# Powering.net
KiCad netlist of a schematic drawn in Altium Designer
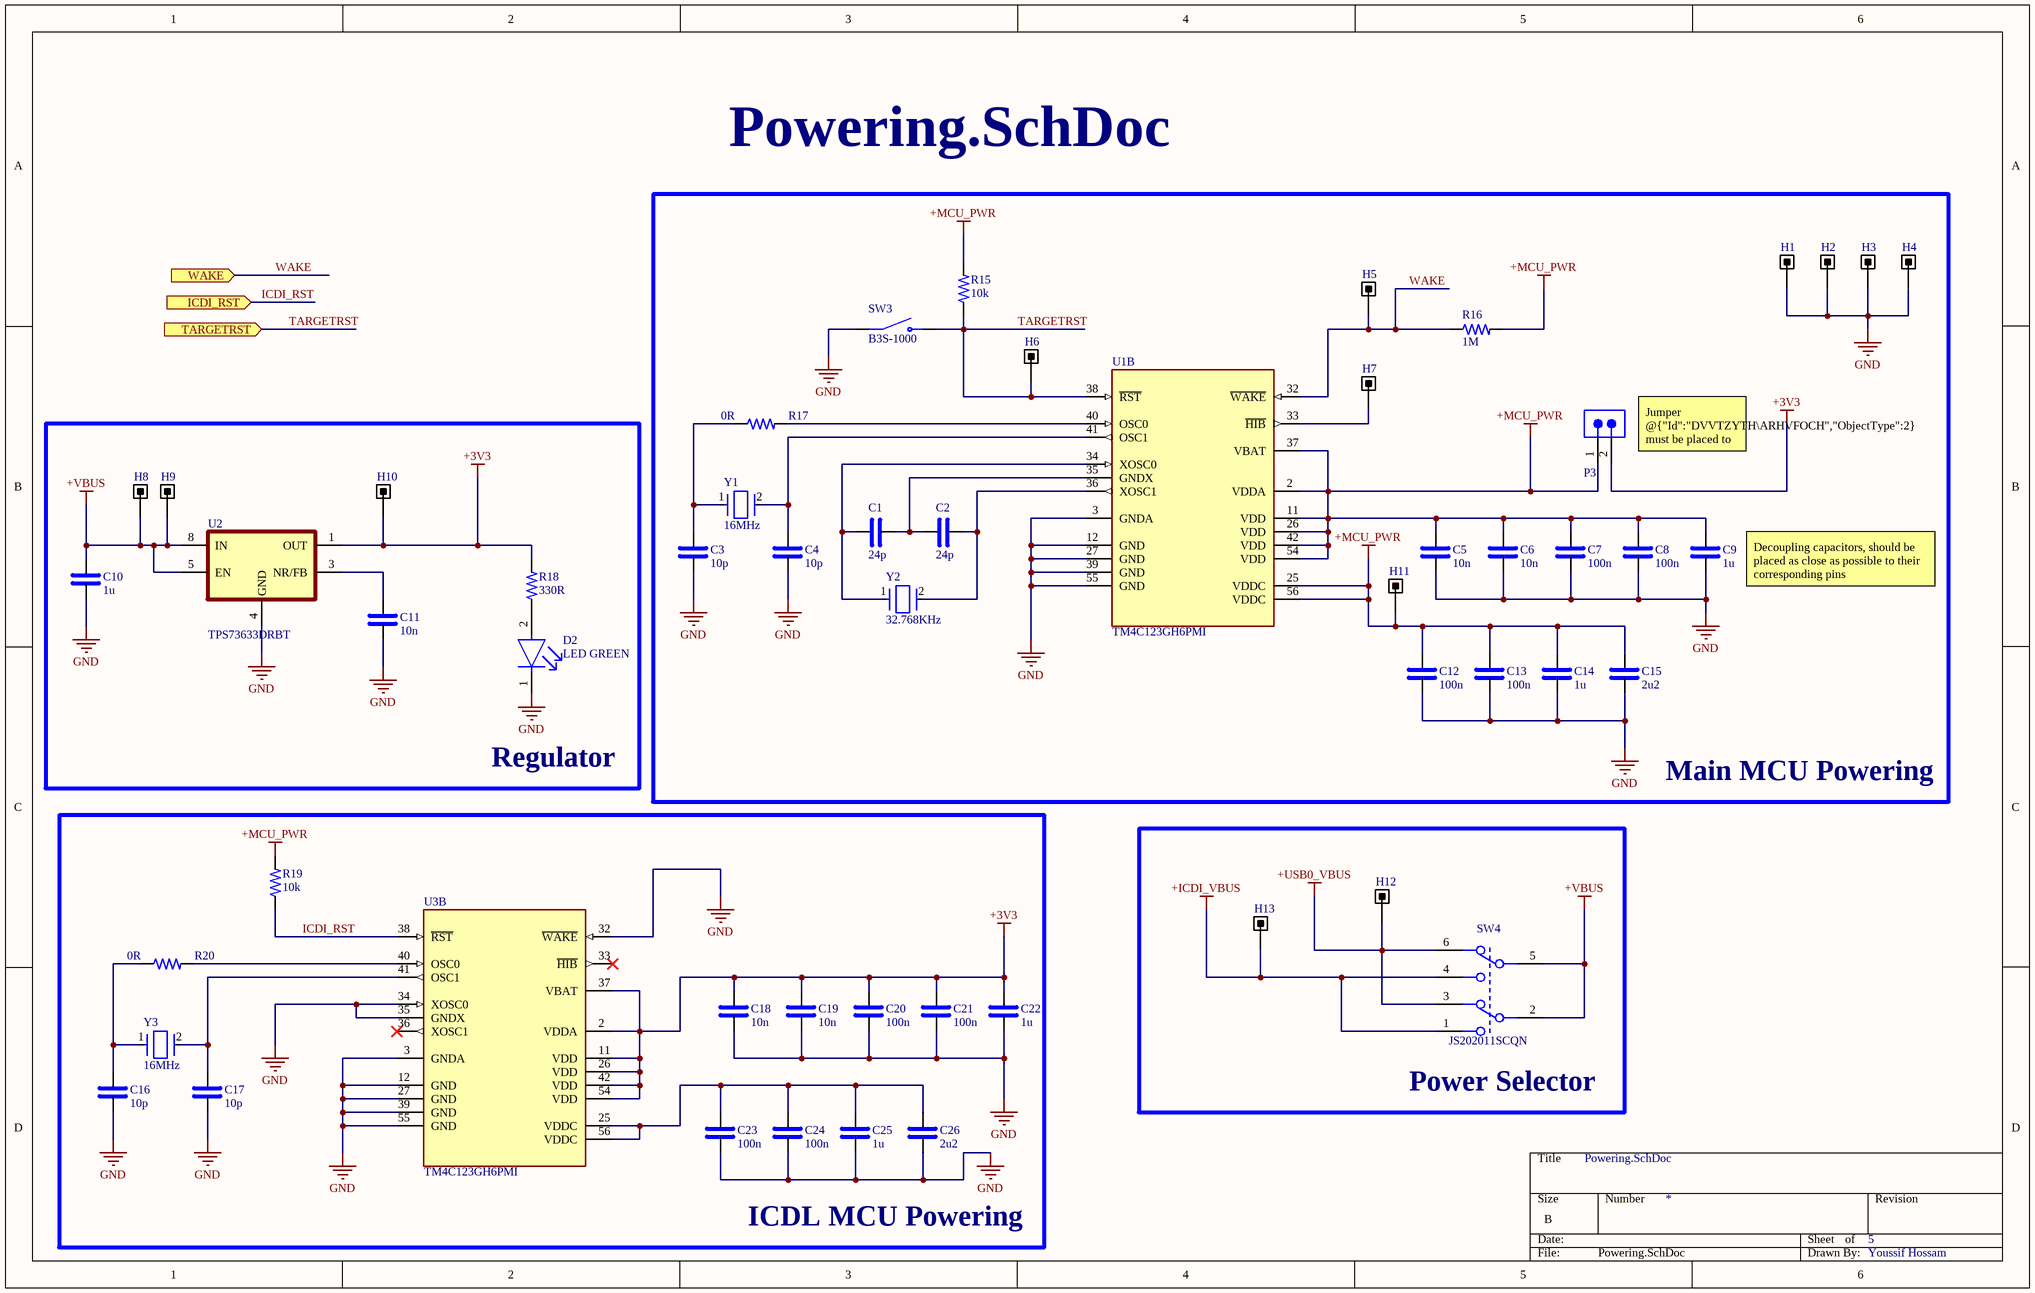
[diagram p0: Powering.SchDoc]

(export (version "E")
  (design (tool "Eeschema 10.0.6"))
  (components
    (comp (ref "C1")
      (value "24p")
      (footprint "0402 CAP")
      (description "24 pF ±5% 50V Ceramic Capacitor C0G, NP0 0402 (1005 Metric)")
      (fields (field (name "PART NUMBER") "C1005C0G1H240J") (field (name "VOLTAGE") "50V"))
      (libsource (lib "Integrated_Library") (part "0402 SMD Capacitor"))
    )
    (comp (ref "C2")
      (value "24p")
      (footprint "0402 CAP")
      (description "24 pF ±5% 50V Ceramic Capacitor C0G, NP0 0402 (1005 Metric)")
      (fields (field (name "PART NUMBER") "C1005C0G1H240J") (field (name "VOLTAGE") "50V"))
      (libsource (lib "Integrated_Library") (part "0402 SMD Capacitor"))
    )
    (comp (ref "C3")
      (value "10p")
      (footprint "0402 CAP")
      (description "10 pF ±5% 50V Ceramic Capacitor C0G, NP0 0402 (1005 Metric)")
      (fields (field (name "PART NUMBER") "GRM1555C1H100JZ01D") (field (name "VOLTAGE") "50V"))
      (libsource (lib "Integrated_Library") (part "0402 SMD Capacitor"))
    )
    (comp (ref "C4")
      (value "10p")
      (footprint "0402 CAP")
      (description "10 pF ±5% 50V Ceramic Capacitor C0G, NP0 0402 (1005 Metric)")
      (fields (field (name "PART NUMBER") "GRM1555C1H100JZ01D") (field (name "VOLTAGE") "50V"))
      (libsource (lib "Integrated_Library") (part "0402 SMD Capacitor"))
    )
    (comp (ref "C5")
      (value "10n")
      (footprint "0402 CAP")
      (fields
        (field (name "MANUFACTURER") "Taiyo Yuden")
        (field (name "MANUFACTURER PART NUMBER") "TMK105B7103KV-F")
      )
      (libsource (lib "Integrated_Library") (part "0402 SMD Capacitor"))
    )
    (comp (ref "C6")
      (value "10n")
      (footprint "0402 CAP")
      (fields
        (field (name "MANUFACTURER") "Taiyo Yuden")
        (field (name "MANUFACTURER PART NUMBER") "TMK105B7103KV-F")
      )
      (libsource (lib "Integrated_Library") (part "0402 SMD Capacitor"))
    )
    (comp (ref "C7")
      (value "100n")
      (footprint "0402 CAP")
      (fields
        (field (name "MANUFACTURER") "Taiyo Yuden")
        (field (name "MANUFACTURER PART NUMBER") "EMK105B7104KV-F")
      )
      (libsource (lib "Integrated_Library") (part "0402 SMD Capacitor"))
    )
    (comp (ref "C8")
      (value "100n")
      (footprint "0402 CAP")
      (fields
        (field (name "MANUFACTURER") "Taiyo Yuden")
        (field (name "MANUFACTURER PART NUMBER") "EMK105B7104KV-F")
      )
      (libsource (lib "Integrated_Library") (part "0402 SMD Capacitor"))
    )
    (comp (ref "C9")
      (value "1u")
      (footprint "0402 CAP")
      (description "Ceramic Capacitor, Ceramic, 10V, 10% +Tol, 10% -Tol, X5R, 15% TC, 1uF, Surface Mount, 0402")
      (fields
        (field (name "MANUFACTURER") "Johanson")
        (field (name "MANUFACTURER PART NUMBER") "100R07X105KV4T")
      )
      (libsource (lib "Integrated_Library") (part "0402 SMD Capacitor"))
    )
    (comp (ref "C10")
      (value "1u")
      (footprint "0402 CAP")
      (description "Ceramic Capacitor, Ceramic, 10V, 10% +Tol, 10% -Tol, X5R, 15% TC, 1uF, Surface Mount, 0402")
      (fields
        (field (name "MANUFACTURER") "Johanson")
        (field (name "MANUFACTURER PART NUMBER") "100R07X105KV4T")
      )
      (libsource (lib "Integrated_Library") (part "0402 SMD Capacitor"))
    )
    (comp (ref "C11")
      (value "10n")
      (footprint "0402 CAP")
      (fields
        (field (name "MANUFACTURER") "Taiyo Yuden")
        (field (name "MANUFACTURER PART NUMBER") "TMK105B7103KV-F")
      )
      (libsource (lib "Integrated_Library") (part "0402 SMD Capacitor"))
    )
    (comp (ref "C12")
      (value "100n")
      (footprint "0402 CAP")
      (fields
        (field (name "MANUFACTURER") "Taiyo Yuden")
        (field (name "MANUFACTURER PART NUMBER") "EMK105B7104KV-F")
      )
      (libsource (lib "Integrated_Library") (part "0402 SMD Capacitor"))
    )
    (comp (ref "C13")
      (value "100n")
      (footprint "0402 CAP")
      (fields
        (field (name "MANUFACTURER") "Taiyo Yuden")
        (field (name "MANUFACTURER PART NUMBER") "EMK105B7104KV-F")
      )
      (libsource (lib "Integrated_Library") (part "0402 SMD Capacitor"))
    )
    (comp (ref "C14")
      (value "1u")
      (footprint "0402 CAP")
      (description "Ceramic Capacitor, Ceramic, 10V, 10% +Tol, 10% -Tol, X5R, 15% TC, 1uF, Surface Mount, 0402")
      (fields
        (field (name "MANUFACTURER") "Johanson")
        (field (name "MANUFACTURER PART NUMBER") "100R07X105KV4T")
      )
      (libsource (lib "Integrated_Library") (part "0402 SMD Capacitor"))
    )
    (comp (ref "C15")
      (value "2u2")
      (footprint "FP-GCJ188-0_2-IPC_C")
      (fields
        (field (name "MANUFACTURER") "Murata")
        (field (name "MANUFACTURER PART NUMBER") "GRM188R61C225KE15D")
      )
      (libsource (lib "Integrated_Library") (part "0603 SMD CAP"))
    )
    (comp (ref "C16")
      (value "10p")
      (footprint "0402 CAP")
      (description "10 pF ±5% 50V Ceramic Capacitor C0G, NP0 0402 (1005 Metric)")
      (fields (field (name "PART NUMBER") "GRM1555C1H100JZ01D") (field (name "VOLTAGE") "50V"))
      (libsource (lib "Integrated_Library") (part "0402 SMD Capacitor"))
    )
    (comp (ref "C17")
      (value "10p")
      (footprint "0402 CAP")
      (description "10 pF ±5% 50V Ceramic Capacitor C0G, NP0 0402 (1005 Metric)")
      (fields (field (name "PART NUMBER") "GRM1555C1H100JZ01D") (field (name "VOLTAGE") "50V"))
      (libsource (lib "Integrated_Library") (part "0402 SMD Capacitor"))
    )
    (comp (ref "C18")
      (value "10n")
      (footprint "0402 CAP")
      (fields
        (field (name "MANUFACTURER") "Taiyo Yuden")
        (field (name "MANUFACTURER PART NUMBER") "TMK105B7103KV-F")
      )
      (libsource (lib "Integrated_Library") (part "0402 SMD Capacitor"))
    )
    (comp (ref "C19")
      (value "10n")
      (footprint "0402 CAP")
      (fields
        (field (name "MANUFACTURER") "Taiyo Yuden")
        (field (name "MANUFACTURER PART NUMBER") "TMK105B7103KV-F")
      )
      (libsource (lib "Integrated_Library") (part "0402 SMD Capacitor"))
    )
    (comp (ref "C20")
      (value "100n")
      (footprint "0402 CAP")
      (fields
        (field (name "MANUFACTURER") "Taiyo Yuden")
        (field (name "MANUFACTURER PART NUMBER") "EMK105B7104KV-F")
      )
      (libsource (lib "Integrated_Library") (part "0402 SMD Capacitor"))
    )
    (comp (ref "C21")
      (value "100n")
      (footprint "0402 CAP")
      (fields
        (field (name "MANUFACTURER") "Taiyo Yuden")
        (field (name "MANUFACTURER PART NUMBER") "EMK105B7104KV-F")
      )
      (libsource (lib "Integrated_Library") (part "0402 SMD Capacitor"))
    )
    (comp (ref "C22")
      (value "1u")
      (footprint "0402 CAP")
      (description "Ceramic Capacitor, Ceramic, 10V, 10% +Tol, 10% -Tol, X5R, 15% TC, 1uF, Surface Mount, 0402")
      (fields
        (field (name "MANUFACTURER") "Johanson")
        (field (name "MANUFACTURER PART NUMBER") "100R07X105KV4T")
      )
      (libsource (lib "Integrated_Library") (part "0402 SMD Capacitor"))
    )
    (comp (ref "C23")
      (value "100n")
      (footprint "0402 CAP")
      (fields
        (field (name "MANUFACTURER") "Taiyo Yuden")
        (field (name "MANUFACTURER PART NUMBER") "EMK105B7104KV-F")
      )
      (libsource (lib "Integrated_Library") (part "0402 SMD Capacitor"))
    )
    (comp (ref "C24")
      (value "100n")
      (footprint "0402 CAP")
      (fields
        (field (name "MANUFACTURER") "Taiyo Yuden")
        (field (name "MANUFACTURER PART NUMBER") "EMK105B7104KV-F")
      )
      (libsource (lib "Integrated_Library") (part "0402 SMD Capacitor"))
    )
    (comp (ref "C25")
      (value "1u")
      (footprint "0402 CAP")
      (description "Ceramic Capacitor, Ceramic, 10V, 10% +Tol, 10% -Tol, X5R, 15% TC, 1uF, Surface Mount, 0402")
      (fields
        (field (name "MANUFACTURER") "Johanson")
        (field (name "MANUFACTURER PART NUMBER") "100R07X105KV4T")
      )
      (libsource (lib "Integrated_Library") (part "0402 SMD Capacitor"))
    )
    (comp (ref "C26")
      (value "2u2")
      (footprint "FP-GCJ188-0_2-IPC_C")
      (fields
        (field (name "MANUFACTURER") "Murata")
        (field (name "MANUFACTURER PART NUMBER") "GRM188R61C225KE15D")
      )
      (libsource (lib "Integrated_Library") (part "0603 SMD CAP"))
    )
    (comp (ref "D2")
      (value "LED GREEN")
      (footprint "FP-LTST-C171GKT-MFG")
      (description "LED GREEN CLEAR CHIP SMD")
      (libsource (lib "Integrated_Library") (part "CMP-22017-000007-1"))
    )
    (comp (ref "H1")
      (value "Test Point")
      (footprint "Test Point")
      (libsource (lib "Integrated_Library") (part "Test Point"))
    )
    (comp (ref "H2")
      (value "Test Point")
      (footprint "Test Point")
      (libsource (lib "Integrated_Library") (part "Test Point"))
    )
    (comp (ref "H3")
      (value "Test Point")
      (footprint "Test Point")
      (libsource (lib "Integrated_Library") (part "Test Point"))
    )
    (comp (ref "H4")
      (value "Test Point")
      (footprint "Test Point")
      (libsource (lib "Integrated_Library") (part "Test Point"))
    )
    (comp (ref "H5")
      (value "Test Point")
      (footprint "Test Point")
      (libsource (lib "Integrated_Library") (part "Test Point"))
    )
    (comp (ref "H6")
      (value "Test Point")
      (footprint "Test Point")
      (libsource (lib "Integrated_Library") (part "Test Point"))
    )
    (comp (ref "H7")
      (value "Test Point")
      (footprint "Test Point")
      (libsource (lib "Integrated_Library") (part "Test Point"))
    )
    (comp (ref "H8")
      (value "Test Point")
      (footprint "Test Point")
      (libsource (lib "Integrated_Library") (part "Test Point"))
    )
    (comp (ref "H9")
      (value "Test Point")
      (footprint "Test Point")
      (libsource (lib "Integrated_Library") (part "Test Point"))
    )
    (comp (ref "H10")
      (value "Test Point")
      (footprint "Test Point")
      (libsource (lib "Integrated_Library") (part "Test Point"))
    )
    (comp (ref "H11")
      (value "Test Point")
      (footprint "Test Point")
      (libsource (lib "Integrated_Library") (part "Test Point"))
    )
    (comp (ref "H12")
      (value "Test Point")
      (footprint "Test Point")
      (libsource (lib "Integrated_Library") (part "Test Point"))
    )
    (comp (ref "H13")
      (value "Test Point")
      (footprint "Test Point")
      (libsource (lib "Integrated_Library") (part "Test Point"))
    )
    (comp (ref "P3")
      (value "61300211121")
      (footprint "61300211121")
      (description "WR-PHD Pin Header, THT, Vertical, pitch 2.54mm, 1 Row, 2P")
      (fields (field (name "MANUFACTURER") "Wurth Elektronik"))
      (libsource (lib "Altium_WR-PHD_rev24a") (part "61300211121"))
    )
    (comp (ref "R15")
      (value "10k")
      (footprint "0402 RES")
      (fields
        (field (name "MANUFACTURER") "Yageo")
        (field (name "MANUFACTURER PART NUMBER") "RC0402FR-0710KL")
        (field (name "POWER") "62.5mW")
      )
      (libsource (lib "Integrated_Library") (part "0402 SMD Resistor"))
    )
    (comp (ref "R16")
      (value "1M")
      (footprint "0402 RES")
      (description "1 MOhms ±1% 0.063W, 1/16W Chip Resistor 0402 (1005 Metric) Thick Film")
      (fields (field (name "PART NUMBER") "MCR01MRTF1004") (field (name "TOLERANCE") "±1%"))
      (libsource (lib "Integrated_Library") (part "0402 SMD Resistor"))
    )
    (comp (ref "R17")
      (value "0R")
      (footprint "FP-ERA3A-IPC_B")
      (description "Fixed Resistor, Metal Glaze/thick Film, 0.1W, 0ohm, Surface Mount, 0603")
      (fields
        (field (name "MANUFACTURER") "Panasonic")
        (field (name "MANUFACTURER PART NUMBER") "ERJ-3GEY0R00V")
      )
      (libsource (lib "Integrated_Library") (part "0603 SMD RES"))
    )
    (comp (ref "R18")
      (value "330R")
      (footprint "0402 RES")
      (fields
        (field (name "MANUFACTURER") "Vishay Dale")
        (field (name "MANUFACTURER PART NUMBER") "RCC0402330RFKED")
      )
      (libsource (lib "Integrated_Library") (part "0402 SMD Resistor"))
    )
    (comp (ref "R19")
      (value "10k")
      (footprint "0402 RES")
      (fields
        (field (name "MANUFACTURER") "Yageo")
        (field (name "MANUFACTURER PART NUMBER") "RC0402FR-0710KL")
        (field (name "POWER") "62.5mW")
      )
      (libsource (lib "Integrated_Library") (part "0402 SMD Resistor"))
    )
    (comp (ref "R20")
      (value "0R")
      (footprint "FP-ERA3A-IPC_B")
      (description "Fixed Resistor, Metal Glaze/thick Film, 0.1W, 0ohm, Surface Mount, 0603")
      (fields
        (field (name "MANUFACTURER") "Panasonic")
        (field (name "MANUFACTURER PART NUMBER") "ERJ-3GEY0R00V")
      )
      (libsource (lib "Integrated_Library") (part "0603 SMD RES"))
    )
    (comp (ref "SW3")
      (value "B3S-1000")
      (footprint "SW_B3S-1000")
      (description "Tactile Switch SPST-NO Top Actuated Surface Mount")
      (fields (field (name "MF") "Omron"))
      (libsource (lib "Integrated_Library") (part "B3S-1000"))
    )
    (comp (ref "SW4")
      (value "JS202011SCQN")
      (footprint "FP-JS202011SCQN-MFG")
      (description "SWITCH SLIDE DPDT 300MA 6V")
      (libsource (lib "Integrated_Library") (part "CMP-2000-05087-3"))
    )
    (comp (ref "U1")
      (value "TM4C123GH6PMI")
      (footprint "QFP50P1200X1200X160-64N")
      (fields (field (name "MF") "Texas Instruments"))
      (libsource (lib "Integrated_Library") (part "TM4C123GH6PMI"))
    )
    (comp (ref "U2")
      (value "TPS73633DRBT")
      (footprint "IC_DRV8601DRBT")
      (libsource (lib "Integrated_Library") (part "TPS73633DRBT"))
    )
    (comp (ref "U3")
      (value "TM4C123GH6PMI")
      (footprint "QFP50P1200X1200X160-64N")
      (fields (field (name "MF") "Texas Instruments"))
      (libsource (lib "Integrated_Library") (part "TM4C123GH6PMI"))
    )
    (comp (ref "Y1")
      (value "16MHz")
      (footprint "FP-ABM3-MFG")
      (description "Crystal 16MHz ±20ppm 18pF SMD-2 5mm x 3.2mm")
      (fields (field (name "TOLERANCE") "20ppm"))
      (libsource (lib "Integrated_Library") (part "CMP-27762-013555-1"))
    )
    (comp (ref "Y2")
      (value "32.768KHz")
      (footprint "FP-AB26TRB-MFG")
      (description "CRYSTAL 32.7680KHZ 12.5PF TH")
      (fields (field (name "TOLERANCE") "20ppm"))
      (libsource (lib "Integrated_Library") (part "CMP-27762-006068-1"))
    )
    (comp (ref "Y3")
      (value "16MHz")
      (footprint "FP-ABM3-MFG")
      (description "Crystal 16MHz ±20ppm 18pF SMD-2 5mm x 3.2mm")
      (fields (field (name "TOLERANCE") "20ppm"))
      (libsource (lib "Integrated_Library") (part "CMP-27762-013555-1"))
    )
  )
  (nets
    (net (code "1") (name "+3V3") (class "Default")
      (node (ref "C18") (pin "2") (pinfunction "2_2") (pintype "passive"))
      (node (ref "C19") (pin "2") (pinfunction "2_2") (pintype "passive"))
      (node (ref "C20") (pin "2") (pinfunction "2_2") (pintype "passive"))
      (node (ref "C21") (pin "2") (pinfunction "2_2") (pintype "passive"))
      (node (ref "C22") (pin "2") (pinfunction "2_2") (pintype "passive"))
      (node (ref "H10") (pin "1") (pinfunction "1_1") (pintype "passive"))
      (node (ref "P3") (pin "2") (pinfunction "2_2") (pintype "passive"))
      (node (ref "R18") (pin "2") (pinfunction "2_2") (pintype "passive"))
      (node (ref "U2") (pin "1") (pinfunction "OUT_1") (pintype "power_in"))
      (node (ref "U3") (pin "11") (pinfunction "VDD_11") (pintype "power_in"))
      (node (ref "U3") (pin "2") (pinfunction "VDDA_2") (pintype "power_in"))
      (node (ref "U3") (pin "26") (pinfunction "VDD_26") (pintype "power_in"))
      (node (ref "U3") (pin "37") (pinfunction "VBAT_37") (pintype "power_in"))
      (node (ref "U3") (pin "42") (pinfunction "VDD_42") (pintype "power_in"))
      (node (ref "U3") (pin "54") (pinfunction "VDD_54") (pintype "power_in"))
    )
    (net (code "2") (name "+ICDI_VBUS") (class "Default")
      (node (ref "H13") (pin "1") (pinfunction "1_1") (pintype "passive"))
      (node (ref "SW4") (pin "1") (pinfunction "1_1") (pintype "passive"))
      (node (ref "SW4") (pin "4") (pinfunction "4_4") (pintype "passive"))
    )
    (net (code "3") (name "+MCU_PWR") (class "Default")
      (node (ref "C12") (pin "2") (pinfunction "2_2") (pintype "passive"))
      (node (ref "C13") (pin "2") (pinfunction "2_2") (pintype "passive"))
      (node (ref "C14") (pin "2") (pinfunction "2_2") (pintype "passive"))
      (node (ref "C15") (pin "2") (pinfunction "2_2") (pintype "passive"))
      (node (ref "C5") (pin "2") (pinfunction "2_2") (pintype "passive"))
      (node (ref "C6") (pin "2") (pinfunction "2_2") (pintype "passive"))
      (node (ref "C7") (pin "2") (pinfunction "2_2") (pintype "passive"))
      (node (ref "C8") (pin "2") (pinfunction "2_2") (pintype "passive"))
      (node (ref "C9") (pin "2") (pinfunction "2_2") (pintype "passive"))
      (node (ref "H11") (pin "1") (pinfunction "1_1") (pintype "passive"))
      (node (ref "P3") (pin "1") (pinfunction "1_1") (pintype "passive"))
      (node (ref "R15") (pin "2") (pinfunction "2_2") (pintype "passive"))
      (node (ref "R16") (pin "2") (pinfunction "2_2") (pintype "passive"))
      (node (ref "R19") (pin "2") (pinfunction "2_2") (pintype "passive"))
      (node (ref "U1") (pin "11") (pinfunction "VDD_11") (pintype "power_in"))
      (node (ref "U1") (pin "2") (pinfunction "VDDA_2") (pintype "power_in"))
      (node (ref "U1") (pin "25") (pinfunction "VDDC_25") (pintype "power_in"))
      (node (ref "U1") (pin "26") (pinfunction "VDD_26") (pintype "power_in"))
      (node (ref "U1") (pin "37") (pinfunction "VBAT_37") (pintype "power_in"))
      (node (ref "U1") (pin "42") (pinfunction "VDD_42") (pintype "power_in"))
      (node (ref "U1") (pin "54") (pinfunction "VDD_54") (pintype "power_in"))
      (node (ref "U1") (pin "56") (pinfunction "VDDC_56") (pintype "power_in"))
    )
    (net (code "4") (name "+USB0_VBUS") (class "Default")
      (node (ref "H12") (pin "1") (pinfunction "1_1") (pintype "passive"))
      (node (ref "SW4") (pin "3") (pinfunction "3_3") (pintype "passive"))
      (node (ref "SW4") (pin "6") (pinfunction "6_6") (pintype "passive"))
    )
    (net (code "5") (name "+VBUS") (class "Default")
      (node (ref "C10") (pin "2") (pinfunction "2_2") (pintype "passive"))
      (node (ref "H8") (pin "1") (pinfunction "1_1") (pintype "passive"))
      (node (ref "H9") (pin "1") (pinfunction "1_1") (pintype "passive"))
      (node (ref "SW4") (pin "2") (pinfunction "2_2") (pintype "passive"))
      (node (ref "SW4") (pin "5") (pinfunction "5_5") (pintype "passive"))
      (node (ref "U2") (pin "5") (pinfunction "EN_5") (pintype "power_in"))
      (node (ref "U2") (pin "8") (pinfunction "IN_8") (pintype "power_in"))
    )
    (net (code "6") (name "/ICDI_RST") (class "Default")
      (node (ref "R19") (pin "1") (pinfunction "1_1") (pintype "passive"))
      (node (ref "U3") (pin "38") (pinfunction "~{RST}_38") (pintype "input"))
    )
    (net (code "7") (name "/TARGETRST") (class "Default")
      (node (ref "H6") (pin "1") (pinfunction "1_1") (pintype "passive"))
      (node (ref "R15") (pin "1") (pinfunction "1_1") (pintype "passive"))
      (node (ref "SW3") (pin "4") (pinfunction "NO_4") (pintype "passive"))
      (node (ref "U1") (pin "38") (pinfunction "~{RST}_38") (pintype "input"))
    )
    (net (code "8") (name "/WAKE") (class "Default")
      (node (ref "H5") (pin "1") (pinfunction "1_1") (pintype "passive"))
      (node (ref "R16") (pin "1") (pinfunction "1_1") (pintype "passive"))
      (node (ref "U1") (pin "32") (pinfunction "~{WAKE}_32") (pintype "input"))
    )
    (net (code "9") (name "GND") (class "Default")
      (node (ref "C10") (pin "1") (pinfunction "1_1") (pintype "passive"))
      (node (ref "C11") (pin "1") (pinfunction "1_1") (pintype "passive"))
      (node (ref "C12") (pin "1") (pinfunction "1_1") (pintype "passive"))
      (node (ref "C13") (pin "1") (pinfunction "1_1") (pintype "passive"))
      (node (ref "C14") (pin "1") (pinfunction "1_1") (pintype "passive"))
      (node (ref "C15") (pin "1") (pinfunction "1_1") (pintype "passive"))
      (node (ref "C16") (pin "1") (pinfunction "1_1") (pintype "passive"))
      (node (ref "C17") (pin "1") (pinfunction "1_1") (pintype "passive"))
      (node (ref "C18") (pin "1") (pinfunction "1_1") (pintype "passive"))
      (node (ref "C19") (pin "1") (pinfunction "1_1") (pintype "passive"))
      (node (ref "C20") (pin "1") (pinfunction "1_1") (pintype "passive"))
      (node (ref "C21") (pin "1") (pinfunction "1_1") (pintype "passive"))
      (node (ref "C22") (pin "1") (pinfunction "1_1") (pintype "passive"))
      (node (ref "C23") (pin "1") (pinfunction "1_1") (pintype "passive"))
      (node (ref "C24") (pin "1") (pinfunction "1_1") (pintype "passive"))
      (node (ref "C25") (pin "1") (pinfunction "1_1") (pintype "passive"))
      (node (ref "C26") (pin "1") (pinfunction "1_1") (pintype "passive"))
      (node (ref "C3") (pin "1") (pinfunction "1_1") (pintype "passive"))
      (node (ref "C4") (pin "1") (pinfunction "1_1") (pintype "passive"))
      (node (ref "C5") (pin "1") (pinfunction "1_1") (pintype "passive"))
      (node (ref "C6") (pin "1") (pinfunction "1_1") (pintype "passive"))
      (node (ref "C7") (pin "1") (pinfunction "1_1") (pintype "passive"))
      (node (ref "C8") (pin "1") (pinfunction "1_1") (pintype "passive"))
      (node (ref "C9") (pin "1") (pinfunction "1_1") (pintype "passive"))
      (node (ref "D2") (pin "1") (pinfunction "C_1") (pintype "passive"))
      (node (ref "H1") (pin "1") (pinfunction "1_1") (pintype "passive"))
      (node (ref "H2") (pin "1") (pinfunction "1_1") (pintype "passive"))
      (node (ref "H3") (pin "1") (pinfunction "1_1") (pintype "passive"))
      (node (ref "H4") (pin "1") (pinfunction "1_1") (pintype "passive"))
      (node (ref "SW3") (pin "2") (pinfunction "COM_2") (pintype "passive"))
      (node (ref "U1") (pin "12") (pinfunction "GND_12") (pintype "power_in"))
      (node (ref "U1") (pin "27") (pinfunction "GND_27") (pintype "power_in"))
      (node (ref "U1") (pin "3") (pinfunction "GNDA_3") (pintype "power_in"))
      (node (ref "U1") (pin "39") (pinfunction "GND_39") (pintype "power_in"))
      (node (ref "U1") (pin "55") (pinfunction "GND_55") (pintype "power_in"))
      (node (ref "U2") (pin "4") (pinfunction "GND_4") (pintype "power_in"))
      (node (ref "U3") (pin "12") (pinfunction "GND_12") (pintype "power_in"))
      (node (ref "U3") (pin "27") (pinfunction "GND_27") (pintype "power_in"))
      (node (ref "U3") (pin "3") (pinfunction "GNDA_3") (pintype "power_in"))
      (node (ref "U3") (pin "32") (pinfunction "~{WAKE}_32") (pintype "input"))
      (node (ref "U3") (pin "34") (pinfunction "XOSC0_34") (pintype "input"))
      (node (ref "U3") (pin "35") (pinfunction "GNDX_35") (pintype "power_in"))
      (node (ref "U3") (pin "39") (pinfunction "GND_39") (pintype "power_in"))
      (node (ref "U3") (pin "55") (pinfunction "GND_55") (pintype "power_in"))
    )
    (net (code "10") (name "Net-(C3-Pad2)") (class "Default")
      (node (ref "C3") (pin "2") (pinfunction "2_2") (pintype "passive"))
      (node (ref "R17") (pin "1") (pinfunction "1_1") (pintype "passive"))
      (node (ref "Y1") (pin "1") (pinfunction "1_1") (pintype "passive"))
    )
    (net (code "11") (name "Net-(C16-Pad2)") (class "Default")
      (node (ref "C16") (pin "2") (pinfunction "2_2") (pintype "passive"))
      (node (ref "R20") (pin "1") (pinfunction "1_1") (pintype "passive"))
      (node (ref "Y3") (pin "1") (pinfunction "1_1") (pintype "passive"))
    )
    (net (code "12") (name "Net-(C23-Pad2)") (class "Default")
      (node (ref "C23") (pin "2") (pinfunction "2_2") (pintype "passive"))
      (node (ref "C24") (pin "2") (pinfunction "2_2") (pintype "passive"))
      (node (ref "C25") (pin "2") (pinfunction "2_2") (pintype "passive"))
      (node (ref "C26") (pin "2") (pinfunction "2_2") (pintype "passive"))
      (node (ref "U3") (pin "25") (pinfunction "VDDC_25") (pintype "power_in"))
      (node (ref "U3") (pin "56") (pinfunction "VDDC_56") (pintype "power_in"))
    )
    (net (code "13") (name "Net-(D2-A)") (class "Default")
      (node (ref "D2") (pin "2") (pinfunction "A_2") (pintype "passive"))
      (node (ref "R18") (pin "1") (pinfunction "1_1") (pintype "passive"))
    )
    (net (code "14") (name "Net-(U1B-GNDX)") (class "Default")
      (node (ref "C1") (pin "1") (pinfunction "1_1") (pintype "passive"))
      (node (ref "C2") (pin "2") (pinfunction "2_2") (pintype "passive"))
      (node (ref "U1") (pin "35") (pinfunction "GNDX_35") (pintype "power_in"))
    )
    (net (code "15") (name "Net-(U1B-OSC0)") (class "Default")
      (node (ref "R17") (pin "2") (pinfunction "2_2") (pintype "passive"))
      (node (ref "U1") (pin "40") (pinfunction "OSC0_40") (pintype "input"))
    )
    (net (code "16") (name "Net-(U1B-OSC1)") (class "Default")
      (node (ref "C4") (pin "2") (pinfunction "2_2") (pintype "passive"))
      (node (ref "U1") (pin "41") (pinfunction "OSC1_41") (pintype "output"))
      (node (ref "Y1") (pin "2") (pinfunction "2_2") (pintype "passive"))
    )
    (net (code "17") (name "Net-(U1B-XOSC0)") (class "Default")
      (node (ref "C1") (pin "2") (pinfunction "2_2") (pintype "passive"))
      (node (ref "U1") (pin "34") (pinfunction "XOSC0_34") (pintype "input"))
      (node (ref "Y2") (pin "1") (pinfunction "1_1") (pintype "passive"))
    )
    (net (code "18") (name "Net-(U1B-XOSC1)") (class "Default")
      (node (ref "C2") (pin "1") (pinfunction "1_1") (pintype "passive"))
      (node (ref "U1") (pin "36") (pinfunction "XOSC1_36") (pintype "output"))
      (node (ref "Y2") (pin "2") (pinfunction "2_2") (pintype "passive"))
    )
    (net (code "19") (name "Net-(U1B-~{HIB})") (class "Default")
      (node (ref "H7") (pin "1") (pinfunction "1_1") (pintype "passive"))
      (node (ref "U1") (pin "33") (pinfunction "~{HIB}_33") (pintype "output"))
    )
    (net (code "20") (name "Net-(U2-NR{slash}FB)") (class "Default")
      (node (ref "C11") (pin "2") (pinfunction "2_2") (pintype "passive"))
      (node (ref "U2") (pin "3") (pinfunction "NR/FB_3") (pintype "passive"))
    )
    (net (code "21") (name "Net-(U3B-OSC0)") (class "Default")
      (node (ref "R20") (pin "2") (pinfunction "2_2") (pintype "passive"))
      (node (ref "U3") (pin "40") (pinfunction "OSC0_40") (pintype "input"))
    )
    (net (code "22") (name "Net-(U3B-OSC1)") (class "Default")
      (node (ref "C17") (pin "2") (pinfunction "2_2") (pintype "passive"))
      (node (ref "U3") (pin "41") (pinfunction "OSC1_41") (pintype "output"))
      (node (ref "Y3") (pin "2") (pinfunction "2_2") (pintype "passive"))
    )
    (net (code "23") (name "unconnected-(U3B-XOSC1-Pad36)") (class "Default")
      (node (ref "U3") (pin "36") (pinfunction "XOSC1_36") (pintype "output+no_connect"))
    )
    (net (code "24") (name "unconnected-(U3B-~{HIB}-Pad33)") (class "Default")
      (node (ref "U3") (pin "33") (pinfunction "~{HIB}_33") (pintype "output+no_connect"))
    )
  )
)
